# buoyancy-engine-connector-male.net
KiCad netlist of a schematic drawn in EAGLE
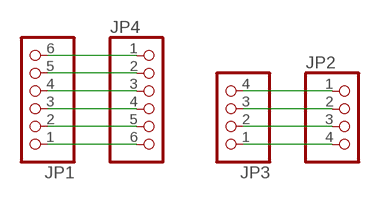
[diagram p0: schematic, sheet 1]

(export (version "E")
  (design (tool "Eeschema 10.0.6"))
  (components
    (comp (ref "JP1")
      (value "PINHD-1X6")
      (footprint "eagle-import:1X06")
      (libsource (lib "eagle-import") (part "PINHD-1X6"))
    )
    (comp (ref "JP2")
      (value "PINHD-1X4")
      (footprint "eagle-import:1X04")
      (libsource (lib "eagle-import") (part "PINHD-1X4"))
    )
    (comp (ref "JP3")
      (value "PINHD-1X4")
      (footprint "eagle-import:1X04")
      (libsource (lib "eagle-import") (part "PINHD-1X4"))
    )
    (comp (ref "JP4")
      (value "PINHD-1X6")
      (footprint "eagle-import:1X06")
      (libsource (lib "eagle-import") (part "PINHD-1X6"))
    )
  )
  (nets
    (net (code "1") (name "Net-(JP1-Pad1)") (class "Default")
      (node (ref "JP1") (pin "1") (pinfunction "1_1") (pintype "passive"))
      (node (ref "JP4") (pin "6") (pinfunction "6_6") (pintype "passive"))
    )
    (net (code "2") (name "Net-(JP1-Pad2)") (class "Default")
      (node (ref "JP1") (pin "2") (pinfunction "2_2") (pintype "passive"))
      (node (ref "JP4") (pin "5") (pinfunction "5_5") (pintype "passive"))
    )
    (net (code "3") (name "Net-(JP1-Pad3)") (class "Default")
      (node (ref "JP1") (pin "3") (pinfunction "3_3") (pintype "passive"))
      (node (ref "JP4") (pin "4") (pinfunction "4_4") (pintype "passive"))
    )
    (net (code "4") (name "Net-(JP1-Pad4)") (class "Default")
      (node (ref "JP1") (pin "4") (pinfunction "4_4") (pintype "passive"))
      (node (ref "JP4") (pin "3") (pinfunction "3_3") (pintype "passive"))
    )
    (net (code "5") (name "Net-(JP1-Pad5)") (class "Default")
      (node (ref "JP1") (pin "5") (pinfunction "5_5") (pintype "passive"))
      (node (ref "JP4") (pin "2") (pinfunction "2_2") (pintype "passive"))
    )
    (net (code "6") (name "Net-(JP1-Pad6)") (class "Default")
      (node (ref "JP1") (pin "6") (pinfunction "6_6") (pintype "passive"))
      (node (ref "JP4") (pin "1") (pinfunction "1_1") (pintype "passive"))
    )
    (net (code "7") (name "Net-(JP2-Pad1)") (class "Default")
      (node (ref "JP2") (pin "1") (pinfunction "1_1") (pintype "passive"))
      (node (ref "JP3") (pin "4") (pinfunction "4_4") (pintype "passive"))
    )
    (net (code "8") (name "Net-(JP2-Pad2)") (class "Default")
      (node (ref "JP2") (pin "2") (pinfunction "2_2") (pintype "passive"))
      (node (ref "JP3") (pin "3") (pinfunction "3_3") (pintype "passive"))
    )
    (net (code "9") (name "Net-(JP2-Pad3)") (class "Default")
      (node (ref "JP2") (pin "3") (pinfunction "3_3") (pintype "passive"))
      (node (ref "JP3") (pin "2") (pinfunction "2_2") (pintype "passive"))
    )
    (net (code "10") (name "Net-(JP2-Pad4)") (class "Default")
      (node (ref "JP2") (pin "4") (pinfunction "4_4") (pintype "passive"))
      (node (ref "JP3") (pin "1") (pinfunction "1_1") (pintype "passive"))
    )
  )
)
